# row_driver.net
KiCad netlist of a schematic drawn in EAGLE
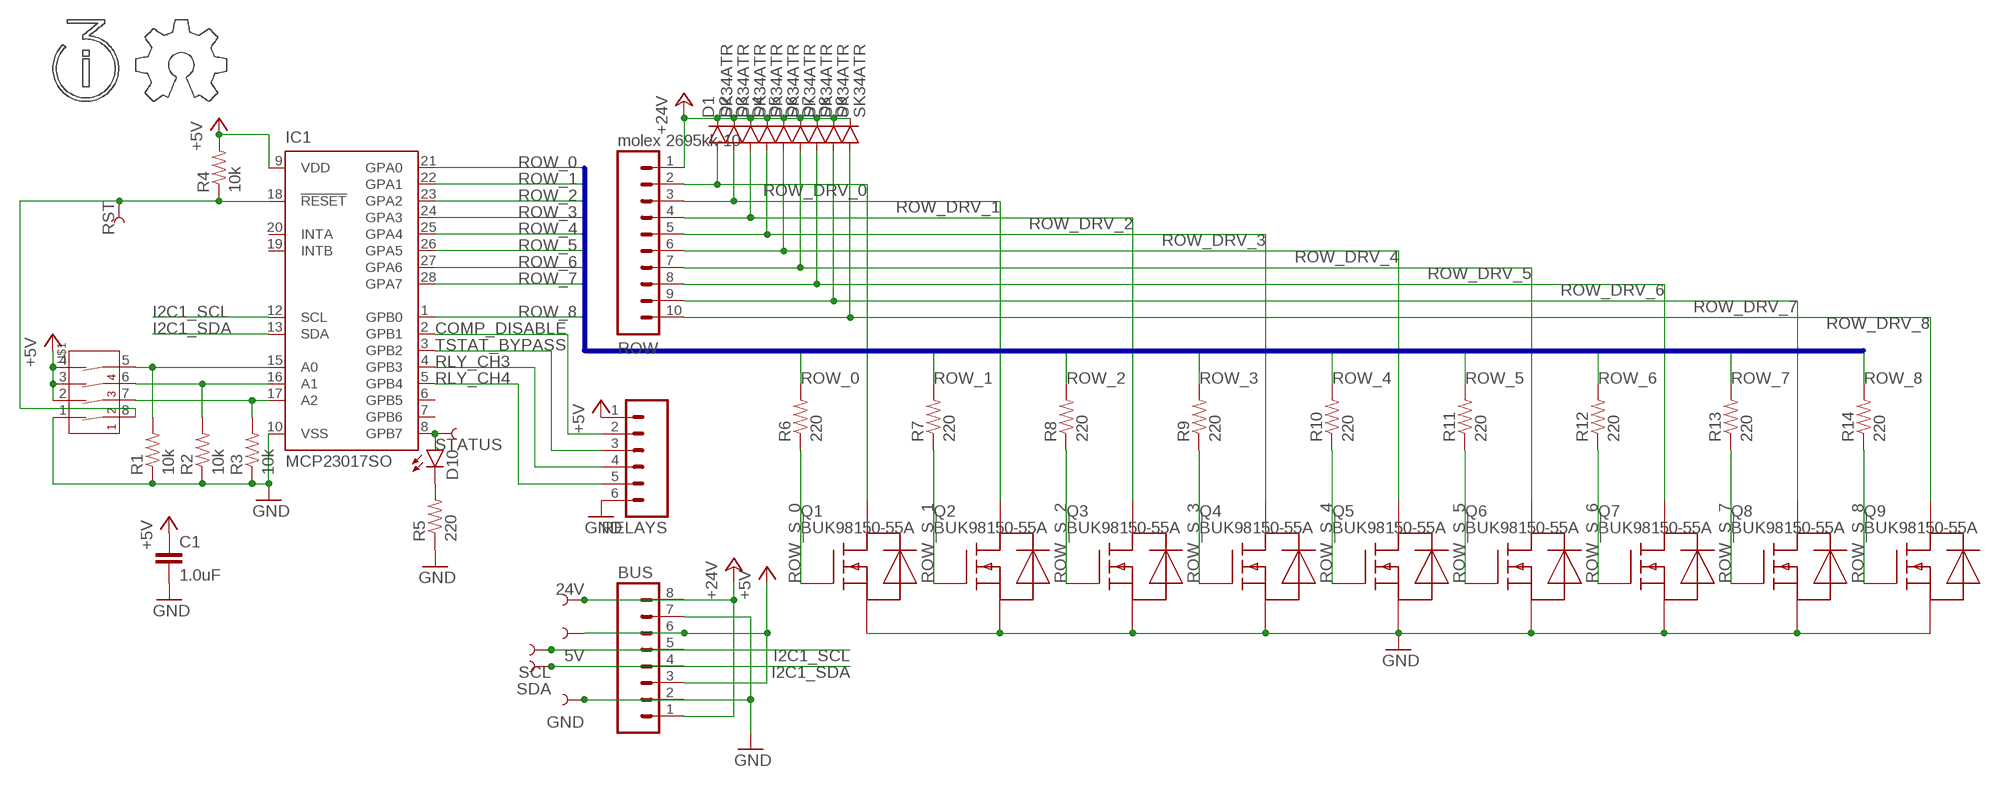
[diagram p0: schematic, sheet 1]

(export (version "E")
  (design (tool "Eeschema 10.0.6"))
  (components
    (comp (ref "5V")
      (value "TEST-POINTTP_15TH_THRU")
      (footprint "eagle-import:TP_15TH")
      (libsource (lib "eagle-import") (part "TEST-POINTTP_15TH_THRU"))
    )
    (comp (ref "24V")
      (value "TEST-POINTTP_15TH_THRU")
      (footprint "eagle-import:TP_15TH")
      (libsource (lib "eagle-import") (part "TEST-POINTTP_15TH_THRU"))
    )
    (comp (ref "BUS")
      (value "M08FEMALE_LOCK")
      (footprint "eagle-import:1X08_FEMALE_LOCK")
      (libsource (lib "eagle-import") (part "M08FEMALE_LOCK"))
    )
    (comp (ref "C1")
      (value "1.0uF")
      (footprint "eagle-import:0603-CAP")
      (libsource (lib "eagle-import") (part "1.0UF-16V-10%(0603)"))
    )
    (comp (ref "D1")
      (value "SK34ATR")
      (footprint "eagle-import:SMA-DIODE")
      (libsource (lib "eagle-import") (part "DIODESMA"))
    )
    (comp (ref "D2")
      (value "SK34ATR")
      (footprint "eagle-import:SMA-DIODE")
      (libsource (lib "eagle-import") (part "DIODESMA"))
    )
    (comp (ref "D3")
      (value "SK34ATR")
      (footprint "eagle-import:SMA-DIODE")
      (libsource (lib "eagle-import") (part "DIODESMA"))
    )
    (comp (ref "D4")
      (value "SK34ATR")
      (footprint "eagle-import:SMA-DIODE")
      (libsource (lib "eagle-import") (part "DIODESMA"))
    )
    (comp (ref "D5")
      (value "SK34ATR")
      (footprint "eagle-import:SMA-DIODE")
      (libsource (lib "eagle-import") (part "DIODESMA"))
    )
    (comp (ref "D6")
      (value "SK34ATR")
      (footprint "eagle-import:SMA-DIODE")
      (libsource (lib "eagle-import") (part "DIODESMA"))
    )
    (comp (ref "D7")
      (value "SK34ATR")
      (footprint "eagle-import:SMA-DIODE")
      (libsource (lib "eagle-import") (part "DIODESMA"))
    )
    (comp (ref "D8")
      (value "SK34ATR")
      (footprint "eagle-import:SMA-DIODE")
      (libsource (lib "eagle-import") (part "DIODESMA"))
    )
    (comp (ref "D9")
      (value "SK34ATR")
      (footprint "eagle-import:SMA-DIODE")
      (libsource (lib "eagle-import") (part "DIODESMA"))
    )
    (comp (ref "D10")
      (value "LED1206")
      (footprint "eagle-import:LED-1206")
      (libsource (lib "eagle-import") (part "LED1206"))
    )
    (comp (ref "GND")
      (value "TEST-POINTTP_15TH_THRU")
      (footprint "eagle-import:TP_15TH")
      (libsource (lib "eagle-import") (part "TEST-POINTTP_15TH_THRU"))
    )
    (comp (ref "IC1")
      (value "MCP23017SO")
      (footprint "eagle-import:SO28W")
      (fields (field (name "MF") "MICROCHIP") (field (name "MPN") "MCP23017-E/SO"))
      (libsource (lib "eagle-import") (part "MCP23017SO"))
    )
    (comp (ref "Q1")
      (value "BUK98150-55A")
      (footprint "eagle-import:SOT223")
      (libsource (lib "eagle-import") (part "BUK98150-55A"))
    )
    (comp (ref "Q2")
      (value "BUK98150-55A")
      (footprint "eagle-import:SOT223")
      (libsource (lib "eagle-import") (part "BUK98150-55A"))
    )
    (comp (ref "Q3")
      (value "BUK98150-55A")
      (footprint "eagle-import:SOT223")
      (libsource (lib "eagle-import") (part "BUK98150-55A"))
    )
    (comp (ref "Q4")
      (value "BUK98150-55A")
      (footprint "eagle-import:SOT223")
      (libsource (lib "eagle-import") (part "BUK98150-55A"))
    )
    (comp (ref "Q5")
      (value "BUK98150-55A")
      (footprint "eagle-import:SOT223")
      (libsource (lib "eagle-import") (part "BUK98150-55A"))
    )
    (comp (ref "Q6")
      (value "BUK98150-55A")
      (footprint "eagle-import:SOT223")
      (libsource (lib "eagle-import") (part "BUK98150-55A"))
    )
    (comp (ref "Q7")
      (value "BUK98150-55A")
      (footprint "eagle-import:SOT223")
      (libsource (lib "eagle-import") (part "BUK98150-55A"))
    )
    (comp (ref "Q8")
      (value "BUK98150-55A")
      (footprint "eagle-import:SOT223")
      (libsource (lib "eagle-import") (part "BUK98150-55A"))
    )
    (comp (ref "Q9")
      (value "BUK98150-55A")
      (footprint "eagle-import:SOT223")
      (libsource (lib "eagle-import") (part "BUK98150-55A"))
    )
    (comp (ref "R1")
      (value "10k")
      (footprint "eagle-import:0805")
      (libsource (lib "eagle-import") (part "RESISTOR0805-RES"))
    )
    (comp (ref "R2")
      (value "10k")
      (footprint "eagle-import:0805")
      (libsource (lib "eagle-import") (part "RESISTOR0805-RES"))
    )
    (comp (ref "R3")
      (value "10k")
      (footprint "eagle-import:0805")
      (libsource (lib "eagle-import") (part "RESISTOR0805-RES"))
    )
    (comp (ref "R4")
      (value "10k")
      (footprint "eagle-import:0805")
      (libsource (lib "eagle-import") (part "RESISTOR0805-RES"))
    )
    (comp (ref "R5")
      (value "220")
      (footprint "eagle-import:0805")
      (libsource (lib "eagle-import") (part "RESISTOR0805-RES"))
    )
    (comp (ref "R6")
      (value "220")
      (footprint "eagle-import:0805")
      (libsource (lib "eagle-import") (part "RESISTOR0805-RES"))
    )
    (comp (ref "R7")
      (value "220")
      (footprint "eagle-import:0805")
      (libsource (lib "eagle-import") (part "RESISTOR0805-RES"))
    )
    (comp (ref "R8")
      (value "220")
      (footprint "eagle-import:0805")
      (libsource (lib "eagle-import") (part "RESISTOR0805-RES"))
    )
    (comp (ref "R9")
      (value "220")
      (footprint "eagle-import:0805")
      (libsource (lib "eagle-import") (part "RESISTOR0805-RES"))
    )
    (comp (ref "R10")
      (value "220")
      (footprint "eagle-import:0805")
      (libsource (lib "eagle-import") (part "RESISTOR0805-RES"))
    )
    (comp (ref "R11")
      (value "220")
      (footprint "eagle-import:0805")
      (libsource (lib "eagle-import") (part "RESISTOR0805-RES"))
    )
    (comp (ref "R12")
      (value "220")
      (footprint "eagle-import:0805")
      (libsource (lib "eagle-import") (part "RESISTOR0805-RES"))
    )
    (comp (ref "R13")
      (value "220")
      (footprint "eagle-import:0805")
      (libsource (lib "eagle-import") (part "RESISTOR0805-RES"))
    )
    (comp (ref "R14")
      (value "220")
      (footprint "eagle-import:0805")
      (libsource (lib "eagle-import") (part "RESISTOR0805-RES"))
    )
    (comp (ref "RELAYS")
      (value "M06LOCK")
      (footprint "eagle-import:1X06_LOCK")
      (libsource (lib "eagle-import") (part "M06LOCK"))
    )
    (comp (ref "ROW")
      (value "molex 2695kk-10")
      (footprint "eagle-import:1X10_LOCK")
      (libsource (lib "eagle-import") (part "M10LOCK"))
    )
    (comp (ref "RST")
      (value "TEST-POINTTP_15TH_THRU")
      (footprint "eagle-import:TP_15TH")
      (libsource (lib "eagle-import") (part "TEST-POINTTP_15TH_THRU"))
    )
    (comp (ref "SCL")
      (value "TEST-POINTTP_15TH_THRU")
      (footprint "eagle-import:TP_15TH")
      (libsource (lib "eagle-import") (part "TEST-POINTTP_15TH_THRU"))
    )
    (comp (ref "SDA")
      (value "TEST-POINTTP_15TH_THRU")
      (footprint "eagle-import:TP_15TH")
      (libsource (lib "eagle-import") (part "TEST-POINTTP_15TH_THRU"))
    )
    (comp (ref "STATUS")
      (value "TEST-POINTTP_15TH_THRU")
      (footprint "eagle-import:TP_15TH")
      (libsource (lib "eagle-import") (part "TEST-POINTTP_15TH_THRU"))
    )
    (comp (ref "U$1")
      (value "4-POS-DIP")
      (footprint "eagle-import:4-POS-DIP-SMD")
      (libsource (lib "eagle-import") (part "4-POS-DIP"))
    )
    (comp (ref "U$2")
      (value "I3LOGO")
      (footprint "eagle-import:I3LOGO")
      (libsource (lib "eagle-import") (part "I3LOGO"))
    )
    (comp (ref "U$4")
      (value "OSHWLOGO")
      (footprint "eagle-import:OSHWLOGO")
      (libsource (lib "eagle-import") (part "OSHWLOGO"))
    )
  )
  (nets
    (net (code "1") (name "+5V") (class "Default")
      (node (ref "5V") (pin "P$1") (pinfunction "1_P$1") (pintype "bidirectional"))
      (node (ref "BUS") (pin "3") (pinfunction "3_3") (pintype "passive"))
      (node (ref "BUS") (pin "6") (pinfunction "6_6") (pintype "passive"))
      (node (ref "C1") (pin "1") (pinfunction "1_1") (pintype "passive"))
      (node (ref "IC1") (pin "9") (pinfunction "VDD_9") (pintype "power_in"))
      (node (ref "R4") (pin "2") (pinfunction "2_2") (pintype "passive"))
      (node (ref "RELAYS") (pin "1") (pinfunction "1_1") (pintype "passive"))
      (node (ref "U$1") (pin "2") (pinfunction "2A_2") (pintype "bidirectional"))
      (node (ref "U$1") (pin "3") (pinfunction "3A_3") (pintype "bidirectional"))
      (node (ref "U$1") (pin "4") (pinfunction "4A_4") (pintype "bidirectional"))
    )
    (net (code "2") (name "+24V") (class "Default")
      (node (ref "24V") (pin "P$1") (pinfunction "1_P$1") (pintype "bidirectional"))
      (node (ref "BUS") (pin "1") (pinfunction "1_1") (pintype "passive"))
      (node (ref "BUS") (pin "8") (pinfunction "8_8") (pintype "passive"))
      (node (ref "D1") (pin "C") (pinfunction "C_C") (pintype "passive"))
      (node (ref "D2") (pin "C") (pinfunction "C_C") (pintype "passive"))
      (node (ref "D3") (pin "C") (pinfunction "C_C") (pintype "passive"))
      (node (ref "D4") (pin "C") (pinfunction "C_C") (pintype "passive"))
      (node (ref "D5") (pin "C") (pinfunction "C_C") (pintype "passive"))
      (node (ref "D6") (pin "C") (pinfunction "C_C") (pintype "passive"))
      (node (ref "D7") (pin "C") (pinfunction "C_C") (pintype "passive"))
      (node (ref "D8") (pin "C") (pinfunction "C_C") (pintype "passive"))
      (node (ref "D9") (pin "C") (pinfunction "C_C") (pintype "passive"))
      (node (ref "ROW") (pin "1") (pinfunction "1_1") (pintype "passive"))
    )
    (net (code "3") (name "/COMP_DISABLE") (class "Default")
      (node (ref "IC1") (pin "2") (pinfunction "GPB1_2") (pintype "bidirectional"))
      (node (ref "RELAYS") (pin "2") (pinfunction "2_2") (pintype "passive"))
    )
    (net (code "4") (name "/I2C1_SCL") (class "Default")
      (node (ref "BUS") (pin "5") (pinfunction "5_5") (pintype "passive"))
      (node (ref "IC1") (pin "12") (pinfunction "SCL_12") (pintype "input"))
      (node (ref "SCL") (pin "P$1") (pinfunction "1_P$1") (pintype "bidirectional"))
    )
    (net (code "5") (name "/I2C1_SDA") (class "Default")
      (node (ref "BUS") (pin "4") (pinfunction "4_4") (pintype "passive"))
      (node (ref "IC1") (pin "13") (pinfunction "SDA_13") (pintype "bidirectional"))
      (node (ref "SDA") (pin "P$1") (pinfunction "1_P$1") (pintype "bidirectional"))
    )
    (net (code "6") (name "/RLY_CH3") (class "Default")
      (node (ref "IC1") (pin "4") (pinfunction "GPB3_4") (pintype "bidirectional"))
      (node (ref "RELAYS") (pin "4") (pinfunction "4_4") (pintype "passive"))
    )
    (net (code "7") (name "/RLY_CH4") (class "Default")
      (node (ref "IC1") (pin "5") (pinfunction "GPB4_5") (pintype "bidirectional"))
      (node (ref "RELAYS") (pin "5") (pinfunction "5_5") (pintype "passive"))
    )
    (net (code "8") (name "/ROW_0") (class "Default")
      (node (ref "IC1") (pin "21") (pinfunction "GPA0_21") (pintype "bidirectional"))
      (node (ref "R6") (pin "2") (pinfunction "2_2") (pintype "passive"))
    )
    (net (code "9") (name "/ROW_1") (class "Default")
      (node (ref "IC1") (pin "22") (pinfunction "GPA1_22") (pintype "bidirectional"))
      (node (ref "R7") (pin "2") (pinfunction "2_2") (pintype "passive"))
    )
    (net (code "10") (name "/ROW_2") (class "Default")
      (node (ref "IC1") (pin "23") (pinfunction "GPA2_23") (pintype "bidirectional"))
      (node (ref "R8") (pin "2") (pinfunction "2_2") (pintype "passive"))
    )
    (net (code "11") (name "/ROW_3") (class "Default")
      (node (ref "IC1") (pin "24") (pinfunction "GPA3_24") (pintype "bidirectional"))
      (node (ref "R9") (pin "2") (pinfunction "2_2") (pintype "passive"))
    )
    (net (code "12") (name "/ROW_4") (class "Default")
      (node (ref "IC1") (pin "25") (pinfunction "GPA4_25") (pintype "bidirectional"))
      (node (ref "R10") (pin "2") (pinfunction "2_2") (pintype "passive"))
    )
    (net (code "13") (name "/ROW_5") (class "Default")
      (node (ref "IC1") (pin "26") (pinfunction "GPA5_26") (pintype "bidirectional"))
      (node (ref "R11") (pin "2") (pinfunction "2_2") (pintype "passive"))
    )
    (net (code "14") (name "/ROW_6") (class "Default")
      (node (ref "IC1") (pin "27") (pinfunction "GPA6_27") (pintype "bidirectional"))
      (node (ref "R12") (pin "2") (pinfunction "2_2") (pintype "passive"))
    )
    (net (code "15") (name "/ROW_7") (class "Default")
      (node (ref "IC1") (pin "28") (pinfunction "GPA7_28") (pintype "bidirectional"))
      (node (ref "R13") (pin "2") (pinfunction "2_2") (pintype "passive"))
    )
    (net (code "16") (name "/ROW_8") (class "Default")
      (node (ref "IC1") (pin "1") (pinfunction "GPB0_1") (pintype "bidirectional"))
      (node (ref "R14") (pin "2") (pinfunction "2_2") (pintype "passive"))
    )
    (net (code "17") (name "/ROW_DRV_0") (class "Default")
      (node (ref "D1") (pin "A") (pinfunction "A_A") (pintype "passive"))
      (node (ref "Q1") (pin "2") (pinfunction "D_2") (pintype "bidirectional"))
      (node (ref "Q1") (pin "4") (pinfunction "D_4") (pintype "bidirectional"))
      (node (ref "ROW") (pin "2") (pinfunction "2_2") (pintype "passive"))
    )
    (net (code "18") (name "/ROW_DRV_1") (class "Default")
      (node (ref "D2") (pin "A") (pinfunction "A_A") (pintype "passive"))
      (node (ref "Q2") (pin "2") (pinfunction "D_2") (pintype "bidirectional"))
      (node (ref "Q2") (pin "4") (pinfunction "D_4") (pintype "bidirectional"))
      (node (ref "ROW") (pin "3") (pinfunction "3_3") (pintype "passive"))
    )
    (net (code "19") (name "/ROW_DRV_2") (class "Default")
      (node (ref "D3") (pin "A") (pinfunction "A_A") (pintype "passive"))
      (node (ref "Q3") (pin "2") (pinfunction "D_2") (pintype "bidirectional"))
      (node (ref "Q3") (pin "4") (pinfunction "D_4") (pintype "bidirectional"))
      (node (ref "ROW") (pin "4") (pinfunction "4_4") (pintype "passive"))
    )
    (net (code "20") (name "/ROW_DRV_3") (class "Default")
      (node (ref "D4") (pin "A") (pinfunction "A_A") (pintype "passive"))
      (node (ref "Q4") (pin "2") (pinfunction "D_2") (pintype "bidirectional"))
      (node (ref "Q4") (pin "4") (pinfunction "D_4") (pintype "bidirectional"))
      (node (ref "ROW") (pin "5") (pinfunction "5_5") (pintype "passive"))
    )
    (net (code "21") (name "/ROW_DRV_4") (class "Default")
      (node (ref "D5") (pin "A") (pinfunction "A_A") (pintype "passive"))
      (node (ref "Q5") (pin "2") (pinfunction "D_2") (pintype "bidirectional"))
      (node (ref "Q5") (pin "4") (pinfunction "D_4") (pintype "bidirectional"))
      (node (ref "ROW") (pin "6") (pinfunction "6_6") (pintype "passive"))
    )
    (net (code "22") (name "/ROW_DRV_5") (class "Default")
      (node (ref "D6") (pin "A") (pinfunction "A_A") (pintype "passive"))
      (node (ref "Q6") (pin "2") (pinfunction "D_2") (pintype "bidirectional"))
      (node (ref "Q6") (pin "4") (pinfunction "D_4") (pintype "bidirectional"))
      (node (ref "ROW") (pin "7") (pinfunction "7_7") (pintype "passive"))
    )
    (net (code "23") (name "/ROW_DRV_6") (class "Default")
      (node (ref "D7") (pin "A") (pinfunction "A_A") (pintype "passive"))
      (node (ref "Q7") (pin "2") (pinfunction "D_2") (pintype "bidirectional"))
      (node (ref "Q7") (pin "4") (pinfunction "D_4") (pintype "bidirectional"))
      (node (ref "ROW") (pin "8") (pinfunction "8_8") (pintype "passive"))
    )
    (net (code "24") (name "/ROW_DRV_7") (class "Default")
      (node (ref "D8") (pin "A") (pinfunction "A_A") (pintype "passive"))
      (node (ref "Q8") (pin "2") (pinfunction "D_2") (pintype "bidirectional"))
      (node (ref "Q8") (pin "4") (pinfunction "D_4") (pintype "bidirectional"))
      (node (ref "ROW") (pin "9") (pinfunction "9_9") (pintype "passive"))
    )
    (net (code "25") (name "/ROW_DRV_8") (class "Default")
      (node (ref "D9") (pin "A") (pinfunction "A_A") (pintype "passive"))
      (node (ref "Q9") (pin "2") (pinfunction "D_2") (pintype "bidirectional"))
      (node (ref "Q9") (pin "4") (pinfunction "D_4") (pintype "bidirectional"))
      (node (ref "ROW") (pin "10") (pinfunction "10_10") (pintype "passive"))
    )
    (net (code "26") (name "/ROW_S_0") (class "Default")
      (node (ref "Q1") (pin "1") (pinfunction "G_1") (pintype "bidirectional"))
      (node (ref "R6") (pin "1") (pinfunction "1_1") (pintype "passive"))
    )
    (net (code "27") (name "/ROW_S_1") (class "Default")
      (node (ref "Q2") (pin "1") (pinfunction "G_1") (pintype "bidirectional"))
      (node (ref "R7") (pin "1") (pinfunction "1_1") (pintype "passive"))
    )
    (net (code "28") (name "/ROW_S_2") (class "Default")
      (node (ref "Q3") (pin "1") (pinfunction "G_1") (pintype "bidirectional"))
      (node (ref "R8") (pin "1") (pinfunction "1_1") (pintype "passive"))
    )
    (net (code "29") (name "/ROW_S_3") (class "Default")
      (node (ref "Q4") (pin "1") (pinfunction "G_1") (pintype "bidirectional"))
      (node (ref "R9") (pin "1") (pinfunction "1_1") (pintype "passive"))
    )
    (net (code "30") (name "/ROW_S_4") (class "Default")
      (node (ref "Q5") (pin "1") (pinfunction "G_1") (pintype "bidirectional"))
      (node (ref "R10") (pin "1") (pinfunction "1_1") (pintype "passive"))
    )
    (net (code "31") (name "/ROW_S_5") (class "Default")
      (node (ref "Q6") (pin "1") (pinfunction "G_1") (pintype "bidirectional"))
      (node (ref "R11") (pin "1") (pinfunction "1_1") (pintype "passive"))
    )
    (net (code "32") (name "/ROW_S_6") (class "Default")
      (node (ref "Q7") (pin "1") (pinfunction "G_1") (pintype "bidirectional"))
      (node (ref "R12") (pin "1") (pinfunction "1_1") (pintype "passive"))
    )
    (net (code "33") (name "/ROW_S_7") (class "Default")
      (node (ref "Q8") (pin "1") (pinfunction "G_1") (pintype "bidirectional"))
      (node (ref "R13") (pin "1") (pinfunction "1_1") (pintype "passive"))
    )
    (net (code "34") (name "/ROW_S_8") (class "Default")
      (node (ref "Q9") (pin "1") (pinfunction "G_1") (pintype "bidirectional"))
      (node (ref "R14") (pin "1") (pinfunction "1_1") (pintype "passive"))
    )
    (net (code "35") (name "/TSTAT_BYPASS") (class "Default")
      (node (ref "IC1") (pin "3") (pinfunction "GPB2_3") (pintype "bidirectional"))
      (node (ref "RELAYS") (pin "3") (pinfunction "3_3") (pintype "passive"))
    )
    (net (code "36") (name "GND") (class "Default")
      (node (ref "BUS") (pin "2") (pinfunction "2_2") (pintype "passive"))
      (node (ref "BUS") (pin "7") (pinfunction "7_7") (pintype "passive"))
      (node (ref "C1") (pin "2") (pinfunction "2_2") (pintype "passive"))
      (node (ref "GND") (pin "P$1") (pinfunction "1_P$1") (pintype "bidirectional"))
      (node (ref "IC1") (pin "10") (pinfunction "VSS_10") (pintype "power_in"))
      (node (ref "Q1") (pin "3") (pinfunction "S_3") (pintype "bidirectional"))
      (node (ref "Q2") (pin "3") (pinfunction "S_3") (pintype "bidirectional"))
      (node (ref "Q3") (pin "3") (pinfunction "S_3") (pintype "bidirectional"))
      (node (ref "Q4") (pin "3") (pinfunction "S_3") (pintype "bidirectional"))
      (node (ref "Q5") (pin "3") (pinfunction "S_3") (pintype "bidirectional"))
      (node (ref "Q6") (pin "3") (pinfunction "S_3") (pintype "bidirectional"))
      (node (ref "Q7") (pin "3") (pinfunction "S_3") (pintype "bidirectional"))
      (node (ref "Q8") (pin "3") (pinfunction "S_3") (pintype "bidirectional"))
      (node (ref "Q9") (pin "3") (pinfunction "S_3") (pintype "bidirectional"))
      (node (ref "R1") (pin "1") (pinfunction "1_1") (pintype "passive"))
      (node (ref "R2") (pin "1") (pinfunction "1_1") (pintype "passive"))
      (node (ref "R3") (pin "1") (pinfunction "1_1") (pintype "passive"))
      (node (ref "R5") (pin "1") (pinfunction "1_1") (pintype "passive"))
      (node (ref "RELAYS") (pin "6") (pinfunction "6_6") (pintype "passive"))
      (node (ref "U$1") (pin "1") (pinfunction "1A_1") (pintype "bidirectional"))
    )
    (net (code "37") (name "Net-(D10-PadC)") (class "Default")
      (node (ref "D10") (pin "C") (pinfunction "C_C") (pintype "passive"))
      (node (ref "R5") (pin "2") (pinfunction "2_2") (pintype "passive"))
    )
    (net (code "38") (name "Net-(IC1-A0)") (class "Default")
      (node (ref "IC1") (pin "15") (pinfunction "A0_15") (pintype "input"))
      (node (ref "R1") (pin "2") (pinfunction "2_2") (pintype "passive"))
      (node (ref "U$1") (pin "5") (pinfunction "4B_5") (pintype "bidirectional"))
    )
    (net (code "39") (name "Net-(IC1-A1)") (class "Default")
      (node (ref "IC1") (pin "16") (pinfunction "A1_16") (pintype "input"))
      (node (ref "R2") (pin "2") (pinfunction "2_2") (pintype "passive"))
      (node (ref "U$1") (pin "6") (pinfunction "3B_6") (pintype "bidirectional"))
    )
    (net (code "40") (name "Net-(IC1-A2)") (class "Default")
      (node (ref "IC1") (pin "17") (pinfunction "A2_17") (pintype "input"))
      (node (ref "R3") (pin "2") (pinfunction "2_2") (pintype "passive"))
      (node (ref "U$1") (pin "7") (pinfunction "2B_7") (pintype "bidirectional"))
    )
    (net (code "41") (name "Net-(IC1-GPB7)") (class "Default")
      (node (ref "D10") (pin "A") (pinfunction "A_A") (pintype "passive"))
      (node (ref "IC1") (pin "8") (pinfunction "GPB7_8") (pintype "bidirectional"))
      (node (ref "STATUS") (pin "P$1") (pinfunction "1_P$1") (pintype "bidirectional"))
    )
    (net (code "42") (name "Net-(IC1-~{RESET})") (class "Default")
      (node (ref "IC1") (pin "18") (pinfunction "~{RESET}_18") (pintype "input"))
      (node (ref "R4") (pin "1") (pinfunction "1_1") (pintype "passive"))
      (node (ref "RST") (pin "P$1") (pinfunction "1_P$1") (pintype "bidirectional"))
      (node (ref "U$1") (pin "8") (pinfunction "1B_8") (pintype "bidirectional"))
    )
    (net (code "43") (name "unconnected-(IC1-GPB5-Pad6)") (class "Default")
      (node (ref "IC1") (pin "6") (pinfunction "GPB5_6") (pintype "bidirectional"))
    )
    (net (code "44") (name "unconnected-(IC1-GPB6-Pad7)") (class "Default")
      (node (ref "IC1") (pin "7") (pinfunction "GPB6_7") (pintype "bidirectional"))
    )
    (net (code "45") (name "unconnected-(IC1-INTA-Pad20)") (class "Default")
      (node (ref "IC1") (pin "20") (pinfunction "INTA_20") (pintype "output"))
    )
    (net (code "46") (name "unconnected-(IC1-INTB-Pad19)") (class "Default")
      (node (ref "IC1") (pin "19") (pinfunction "INTB_19") (pintype "output"))
    )
  )
)
